# Controller_Nano_1_5.net
KiCad netlist of a schematic drawn in EAGLE
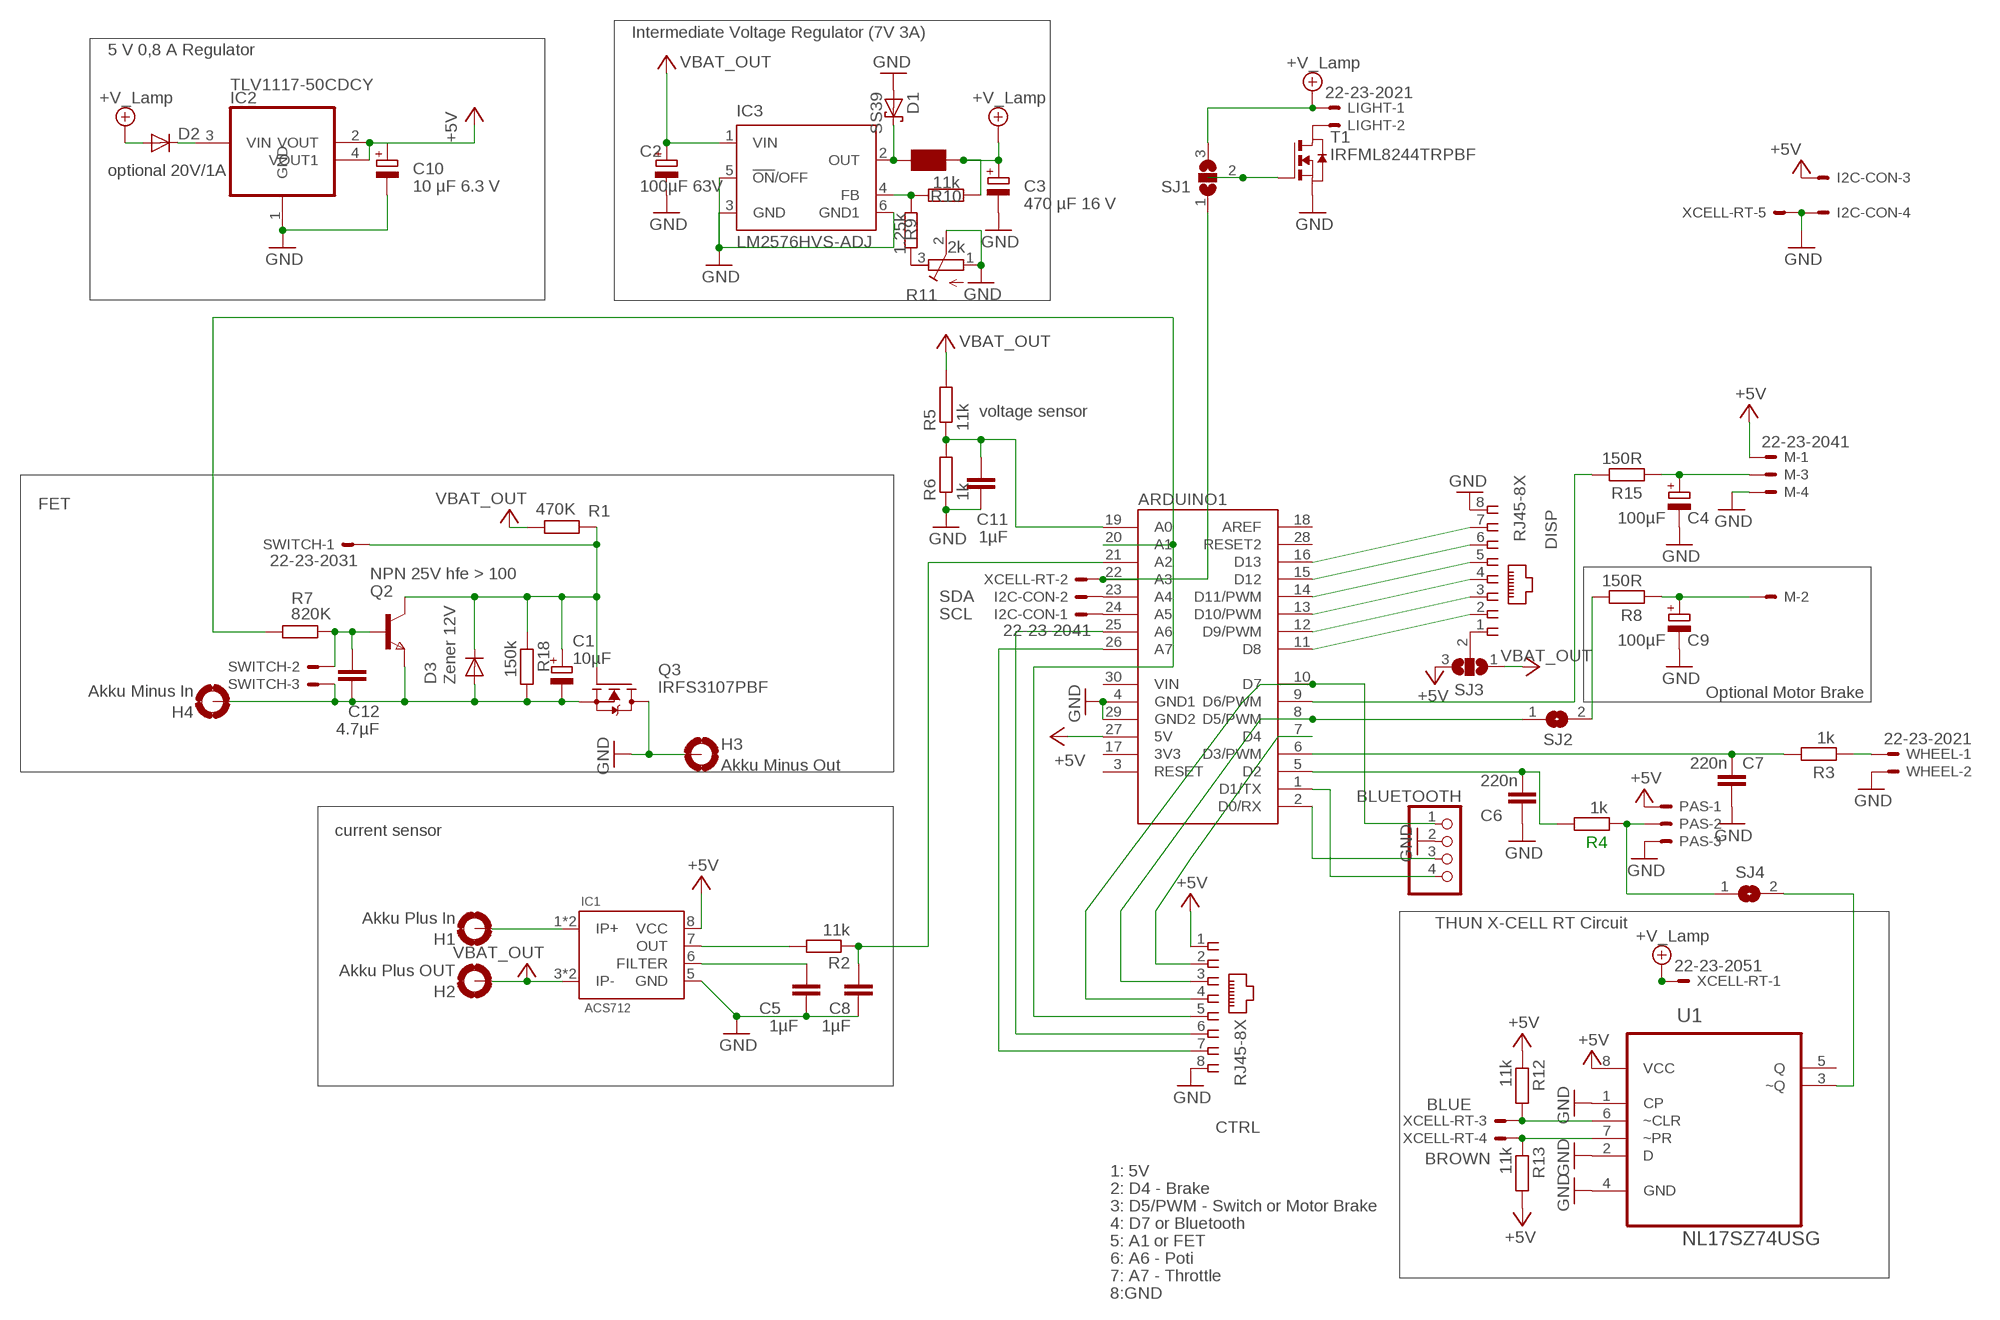
[diagram p0: schematic, sheet 1]

(export (version "E")
  (design (tool "Eeschema 10.0.6"))
  (components
    (comp (ref "ARDUINO1")
      (value "ARDUINO_NANO_CHECKED")
      (footprint "eagle-import:ARDUINO_NANO_CHECKED")
      (libsource (lib "eagle-import") (part "ARDUINO_NANO_CHECKED"))
    )
    (comp (ref "BLUETOOTH")
      (value "PINHD-1X4")
      (footprint "eagle-import:1X04")
      (libsource (lib "eagle-import") (part "PINHD-1X4"))
    )
    (comp (ref "C1")
      (value "10µF")
      (footprint "eagle-import:E2-5")
      (libsource (lib "eagle-import") (part "CPOL-EUE2-5"))
    )
    (comp (ref "C2")
      (value "100µF 63V")
      (footprint "eagle-import:E3,5-8")
      (libsource (lib "eagle-import") (part "CPOL-EUE3.5-8"))
    )
    (comp (ref "C3")
      (value "470 µF 16 V")
      (footprint "eagle-import:E3,5-8")
      (libsource (lib "eagle-import") (part "CPOL-EUE3.5-8"))
    )
    (comp (ref "C4")
      (value "100µF")
      (footprint "eagle-import:E2-5")
      (libsource (lib "eagle-import") (part "CPOL-EUE2-5"))
    )
    (comp (ref "C5")
      (value "1µF")
      (footprint "eagle-import:C0805")
      (libsource (lib "eagle-import") (part "C-EUC0805"))
    )
    (comp (ref "C6")
      (value "220n")
      (footprint "eagle-import:C0805")
      (libsource (lib "eagle-import") (part "C-EUC0805"))
    )
    (comp (ref "C7")
      (value "220n")
      (footprint "eagle-import:C0805")
      (libsource (lib "eagle-import") (part "C-EUC0805"))
    )
    (comp (ref "C8")
      (value "1µF")
      (footprint "eagle-import:C0805")
      (libsource (lib "eagle-import") (part "C-EUC0805"))
    )
    (comp (ref "C9")
      (value "100µF")
      (footprint "eagle-import:E2-5")
      (libsource (lib "eagle-import") (part "CPOL-EUE2-5"))
    )
    (comp (ref "C10")
      (value "10 µF 6.3 V")
      (footprint "eagle-import:E2-5")
      (libsource (lib "eagle-import") (part "CPOL-EUE2-5"))
    )
    (comp (ref "C11")
      (value "1µF")
      (footprint "eagle-import:C0805")
      (libsource (lib "eagle-import") (part "C-EUC0805"))
    )
    (comp (ref "C12")
      (value "4.7µF")
      (footprint "eagle-import:C0805")
      (libsource (lib "eagle-import") (part "C-EUC0805"))
    )
    (comp (ref "CTRL")
      (value "RJ45-8X")
      (footprint "eagle-import:RJ45-NO-SHIELD")
      (libsource (lib "eagle-import") (part "RJ45-8X"))
    )
    (comp (ref "D1")
      (value "SS39")
      (footprint "eagle-import:SMC")
      (libsource (lib "eagle-import") (part "SCHOTTKY-DIODESMC"))
    )
    (comp (ref "D2")
      (value "optional 20V/1A")
      (footprint "eagle-import:DO-214AC")
      (libsource (lib "eagle-import") (part "DIODE-DO-214AC"))
    )
    (comp (ref "D3")
      (value "Zener 12V")
      (footprint "eagle-import:SOD323-W")
      (libsource (lib "eagle-import") (part "DIODE-SOD323-W"))
    )
    (comp (ref "DISP")
      (value "RJ45-8X")
      (footprint "eagle-import:RJ45-NO-SHIELD")
      (libsource (lib "eagle-import") (part "RJ45-8X"))
    )
    (comp (ref "H1")
      (value "Akku Plus In")
      (footprint "eagle-import:2,8-PAD")
      (libsource (lib "eagle-import") (part "MOUNT-PAD-ROUND2.8"))
    )
    (comp (ref "H2")
      (value "Akku Plus OUT")
      (footprint "eagle-import:2,8-PAD")
      (libsource (lib "eagle-import") (part "MOUNT-PAD-ROUND2.8"))
    )
    (comp (ref "H3")
      (value "Akku Minus Out")
      (footprint "eagle-import:2,8-PAD")
      (libsource (lib "eagle-import") (part "MOUNT-PAD-ROUND2.8"))
    )
    (comp (ref "H4")
      (value "Akku Minus In")
      (footprint "eagle-import:2,8-PAD")
      (libsource (lib "eagle-import") (part "MOUNT-PAD-ROUND2.8"))
    )
    (comp (ref "I2C-CON")
      (value "22-23-2041")
      (footprint "eagle-import:22-23-2041")
      (fields (field (name "MF") "MOLEX"))
      (libsource (lib "eagle-import") (part "22-23-2041"))
    )
    (comp (ref "IC1")
      (value "ACS712")
      (footprint "eagle-import:MARTIN-SMD-IC_SO-8")
      (libsource (lib "eagle-import") (part "MARTIN-SMD-IC_ACS712"))
    )
    (comp (ref "IC2")
      (value "TLV1117-50CDCY")
      (footprint "eagle-import:SOT223")
      (fields (field (name "MPN") "REG1117"))
      (libsource (lib "eagle-import") (part "REG1117"))
    )
    (comp (ref "IC3")
      (value "LM2576HVS-ADJ")
      (footprint "eagle-import:TO263-5")
      (fields (field (name "MF") "NATIONAL SEMICONDUCTOR") (field (name "MPN") "LM2596S-ADJ/NOPB"))
      (libsource (lib "eagle-import") (part "LM2596S"))
    )
    (comp (ref "LIGHT")
      (value "22-23-2021")
      (footprint "eagle-import:22-23-2021")
      (fields
        (field (name "MF") "MOLEX")
        (field (name "MF_1") "MOLEX")
        (field (name "MPN") "22-23-2021")
        (field (name "OC_FARNELL") "1462926")
        (field (name "OC_NEWARK") "25C3832")
      )
      (libsource (lib "eagle-import") (part "22-23-2021"))
    )
    (comp (ref "M")
      (value "22-23-2041")
      (footprint "eagle-import:22-23-2041")
      (fields
        (field (name "MF") "MOLEX")
        (field (name "MPN") "22-23-2041")
        (field (name "OC_FARNELL") "1462920")
        (field (name "OC_NEWARK") "38C0355")
      )
      (libsource (lib "eagle-import") (part "22-23-2041"))
    )
    (comp (ref "PAS")
      (value "22-23-2031")
      (footprint "eagle-import:22-23-2031")
      (fields (field (name "MF") "MOLEX"))
      (libsource (lib "eagle-import") (part "22-23-2031"))
    )
    (comp (ref "Q2")
      (value "NPN 25V hfe > 100")
      (footprint "eagle-import:SOT-23")
      (fields (field (name "MPN") "DSS20201L-7"))
      (libsource (lib "eagle-import") (part "NPNSOT23"))
    )
    (comp (ref "Q3")
      (value "IRFS3107PBF")
      (footprint "eagle-import:TRANSISTOR-FET_TO263")
      (libsource (lib "eagle-import") (part "BUK663R7-75C"))
    )
    (comp (ref "R1")
      (value "470K")
      (footprint "eagle-import:R1206")
      (libsource (lib "eagle-import") (part "R-EU_R1206"))
    )
    (comp (ref "R2")
      (value "11k")
      (footprint "eagle-import:R1206")
      (libsource (lib "eagle-import") (part "R-EU_R1206"))
    )
    (comp (ref "R3")
      (value "1k")
      (footprint "eagle-import:R1206")
      (libsource (lib "eagle-import") (part "R-EU_R1206"))
    )
    (comp (ref "R4")
      (value "1k")
      (footprint "eagle-import:R1206")
      (libsource (lib "eagle-import") (part "R-EU_R1206"))
    )
    (comp (ref "R5")
      (value "11k")
      (footprint "eagle-import:R1206")
      (libsource (lib "eagle-import") (part "R-EU_R1206"))
    )
    (comp (ref "R6")
      (value "1k")
      (footprint "eagle-import:R1206")
      (libsource (lib "eagle-import") (part "R-EU_R1206"))
    )
    (comp (ref "R7")
      (value "820K")
      (footprint "eagle-import:R1206")
      (libsource (lib "eagle-import") (part "R-EU_R1206"))
    )
    (comp (ref "R8")
      (value "150R")
      (footprint "eagle-import:R1206")
      (libsource (lib "eagle-import") (part "R-EU_R1206"))
    )
    (comp (ref "R9")
      (value "1.25k")
      (footprint "eagle-import:R1206")
      (libsource (lib "eagle-import") (part "R-EU_R1206"))
    )
    (comp (ref "R10")
      (value "11k")
      (footprint "eagle-import:R1206")
      (libsource (lib "eagle-import") (part "R-EU_R1206"))
    )
    (comp (ref "R11")
      (value "2k")
      (footprint "eagle-import:RTRIM3103")
      (libsource (lib "eagle-import") (part "R-TRIMM3103"))
    )
    (comp (ref "R12")
      (value "11k")
      (footprint "eagle-import:R1206")
      (libsource (lib "eagle-import") (part "R-EU_R1206"))
    )
    (comp (ref "R13")
      (value "11k")
      (footprint "eagle-import:R1206")
      (libsource (lib "eagle-import") (part "R-EU_R1206"))
    )
    (comp (ref "R15")
      (value "150R")
      (footprint "eagle-import:R1206")
      (libsource (lib "eagle-import") (part "R-EU_R1206"))
    )
    (comp (ref "R18")
      (value "150k")
      (footprint "eagle-import:R1206")
      (libsource (lib "eagle-import") (part "R-EU_R1206"))
    )
    (comp (ref "SJ1")
      (value "SJ2WW")
      (footprint "eagle-import:SJ_2W")
      (libsource (lib "eagle-import") (part "SJ2WW"))
    )
    (comp (ref "SJ2") (value "SJ") (footprint "eagle-import:SJ") (libsource (lib "eagle-import") (part "SJ")))
    (comp (ref "SJ3")
      (value "SJ2WW")
      (footprint "eagle-import:SJ_2W")
      (libsource (lib "eagle-import") (part "SJ2WW"))
    )
    (comp (ref "SJ4") (value "SJ") (footprint "eagle-import:SJ") (libsource (lib "eagle-import") (part "SJ")))
    (comp (ref "SWITCH")
      (value "22-23-2031")
      (footprint "eagle-import:22-23-2031")
      (fields
        (field (name "MF") "MOLEX")
        (field (name "MPN") "22-23-2031")
        (field (name "OC_FARNELL") "1462950")
        (field (name "OC_NEWARK") "30C0862")
      )
      (libsource (lib "eagle-import") (part "22-23-2031"))
    )
    (comp (ref "T1")
      (value "IRFML8244TRPBF")
      (footprint "eagle-import:SOT-23")
      (libsource (lib "eagle-import") (part "NMOSSOT23"))
    )
    (comp (ref "U$1")
      (value "PIST-151")
      (footprint "eagle-import:PIST-151")
      (libsource (lib "eagle-import") (part "PIST-151"))
    )
    (comp (ref "U1")
      (value "NL17SZ74USG")
      (footprint "eagle-import:SOP50P310X90-8N")
      (libsource (lib "eagle-import") (part "NL17SZ74USG"))
    )
    (comp (ref "WHEEL")
      (value "22-23-2021")
      (footprint "eagle-import:22-23-2021")
      (fields (field (name "MF") "MOLEX"))
      (libsource (lib "eagle-import") (part "22-23-2021"))
    )
    (comp (ref "XCELL-RT")
      (value "22-23-2051")
      (footprint "eagle-import:22-23-2051")
      (fields (field (name "MF") "MOLEX"))
      (libsource (lib "eagle-import") (part "22-23-2051"))
    )
  )
  (nets
    (net (code "1") (name "+5V") (class "Default")
      (node (ref "ARDUINO1") (pin "27") (pinfunction "5V_27") (pintype "power_in"))
      (node (ref "C10") (pin "+") (pinfunction "+_+") (pintype "passive"))
      (node (ref "CTRL") (pin "1") (pinfunction "1_1") (pintype "passive"))
      (node (ref "I2C-CON") (pin "3") (pinfunction "S_3") (pintype "passive"))
      (node (ref "IC1") (pin "8") (pinfunction "VCC_8") (pintype "power_in"))
      (node (ref "IC2") (pin "2") (pinfunction "VOUT_2") (pintype "output"))
      (node (ref "IC2") (pin "4") (pinfunction "VOUT1_4") (pintype "output"))
      (node (ref "M") (pin "1") (pinfunction "S_1") (pintype "passive"))
      (node (ref "PAS") (pin "1") (pinfunction "S_1") (pintype "passive"))
      (node (ref "R12") (pin "1") (pinfunction "1_1") (pintype "passive"))
      (node (ref "R13") (pin "2") (pinfunction "2_2") (pintype "passive"))
      (node (ref "SJ3") (pin "3") (pinfunction "3_3") (pintype "passive"))
      (node (ref "U1") (pin "8") (pinfunction "VCC_8") (pintype "power_in"))
    )
    (net (code "2") (name "+V_Lamp") (class "Default")
      (node (ref "C3") (pin "+") (pinfunction "+_+") (pintype "passive"))
      (node (ref "D2") (pin "A") (pinfunction "A_A") (pintype "passive"))
      (node (ref "LIGHT") (pin "1") (pinfunction "S_1") (pintype "passive"))
      (node (ref "R10") (pin "1") (pinfunction "1_1") (pintype "passive"))
      (node (ref "SJ1") (pin "3") (pinfunction "3_3") (pintype "passive"))
      (node (ref "U$1") (pin "P$2") (pinfunction "P$2_P$2") (pintype "bidirectional"))
      (node (ref "XCELL-RT") (pin "1") (pinfunction "S_1") (pintype "passive"))
    )
    (net (code "3") (name "/3V3") (class "Default")
      (node (ref "ARDUINO1") (pin "17") (pinfunction "3V3_17") (pintype "power_in"))
    )
    (net (code "4") (name "GND") (class "Default")
      (node (ref "ARDUINO1") (pin "29") (pinfunction "GND2_29") (pintype "power_in"))
      (node (ref "ARDUINO1") (pin "4") (pinfunction "GND1_4") (pintype "power_in"))
      (node (ref "BLUETOOTH") (pin "2") (pinfunction "2_2") (pintype "passive"))
      (node (ref "C10") (pin "-") (pinfunction "-_-") (pintype "passive"))
      (node (ref "C11") (pin "2") (pinfunction "2_2") (pintype "passive"))
      (node (ref "C2") (pin "-") (pinfunction "-_-") (pintype "passive"))
      (node (ref "C3") (pin "-") (pinfunction "-_-") (pintype "passive"))
      (node (ref "C4") (pin "-") (pinfunction "-_-") (pintype "passive"))
      (node (ref "C5") (pin "2") (pinfunction "2_2") (pintype "passive"))
      (node (ref "C6") (pin "2") (pinfunction "2_2") (pintype "passive"))
      (node (ref "C7") (pin "2") (pinfunction "2_2") (pintype "passive"))
      (node (ref "C8") (pin "2") (pinfunction "2_2") (pintype "passive"))
      (node (ref "C9") (pin "-") (pinfunction "-_-") (pintype "passive"))
      (node (ref "CTRL") (pin "8") (pinfunction "8_8") (pintype "passive"))
      (node (ref "D1") (pin "A") (pinfunction "A_A") (pintype "passive"))
      (node (ref "DISP") (pin "8") (pinfunction "8_8") (pintype "passive"))
      (node (ref "H3") (pin "B2,8") (pinfunction "MOUNT_B2,8") (pintype "passive"))
      (node (ref "I2C-CON") (pin "4") (pinfunction "S_4") (pintype "passive"))
      (node (ref "IC1") (pin "5") (pinfunction "GND_5") (pintype "power_in"))
      (node (ref "IC2") (pin "1") (pinfunction "GND_1") (pintype "power_in"))
      (node (ref "IC3") (pin "3") (pinfunction "GND_3") (pintype "power_in"))
      (node (ref "IC3") (pin "5") (pinfunction "~{ON}/OFF_5") (pintype "input"))
      (node (ref "IC3") (pin "6") (pinfunction "GND1_6") (pintype "power_in"))
      (node (ref "M") (pin "4") (pinfunction "S_4") (pintype "passive"))
      (node (ref "PAS") (pin "3") (pinfunction "S_3") (pintype "passive"))
      (node (ref "Q3") (pin "2D") (pinfunction "D_2D") (pintype "passive"))
      (node (ref "R11") (pin "1") (pinfunction "E_1") (pintype "passive"))
      (node (ref "R11") (pin "2") (pinfunction "S_2") (pintype "passive"))
      (node (ref "R6") (pin "1") (pinfunction "1_1") (pintype "passive"))
      (node (ref "T1") (pin "2") (pinfunction "S_2") (pintype "passive"))
      (node (ref "U1") (pin "1") (pinfunction "CP_1") (pintype "input"))
      (node (ref "U1") (pin "2") (pinfunction "D_2") (pintype "input"))
      (node (ref "U1") (pin "4") (pinfunction "GND_4") (pintype "passive"))
      (node (ref "WHEEL") (pin "2") (pinfunction "S_2") (pintype "passive"))
      (node (ref "XCELL-RT") (pin "5") (pinfunction "S_5") (pintype "passive"))
    )
    (net (code "5") (name "Net-(ARDUINO1-A0)") (class "Default")
      (node (ref "ARDUINO1") (pin "19") (pinfunction "A0_19") (pintype "bidirectional"))
      (node (ref "C11") (pin "1") (pinfunction "1_1") (pintype "passive"))
      (node (ref "R5") (pin "1") (pinfunction "1_1") (pintype "passive"))
      (node (ref "R6") (pin "2") (pinfunction "2_2") (pintype "passive"))
    )
    (net (code "6") (name "Net-(ARDUINO1-A1)") (class "Default")
      (node (ref "ARDUINO1") (pin "20") (pinfunction "A1_20") (pintype "bidirectional"))
      (node (ref "CTRL") (pin "5") (pinfunction "5_5") (pintype "passive"))
      (node (ref "R7") (pin "2") (pinfunction "2_2") (pintype "passive"))
    )
    (net (code "7") (name "Net-(ARDUINO1-A2)") (class "Default")
      (node (ref "ARDUINO1") (pin "21") (pinfunction "A2_21") (pintype "bidirectional"))
      (node (ref "C8") (pin "1") (pinfunction "1_1") (pintype "passive"))
      (node (ref "R2") (pin "1") (pinfunction "1_1") (pintype "passive"))
    )
    (net (code "8") (name "Net-(ARDUINO1-A3)") (class "Default")
      (node (ref "ARDUINO1") (pin "22") (pinfunction "A3_22") (pintype "bidirectional"))
      (node (ref "SJ1") (pin "1") (pinfunction "1_1") (pintype "passive"))
      (node (ref "XCELL-RT") (pin "2") (pinfunction "S_2") (pintype "passive"))
    )
    (net (code "9") (name "Net-(ARDUINO1-A4)") (class "Default")
      (node (ref "ARDUINO1") (pin "23") (pinfunction "A4_23") (pintype "bidirectional"))
      (node (ref "I2C-CON") (pin "2") (pinfunction "S_2") (pintype "passive"))
    )
    (net (code "10") (name "Net-(ARDUINO1-A5)") (class "Default")
      (node (ref "ARDUINO1") (pin "24") (pinfunction "A5_24") (pintype "bidirectional"))
      (node (ref "I2C-CON") (pin "1") (pinfunction "S_1") (pintype "passive"))
    )
    (net (code "11") (name "Net-(ARDUINO1-A6)") (class "Default")
      (node (ref "ARDUINO1") (pin "25") (pinfunction "A6_25") (pintype "bidirectional"))
      (node (ref "CTRL") (pin "6") (pinfunction "6_6") (pintype "passive"))
    )
    (net (code "12") (name "Net-(ARDUINO1-A7)") (class "Default")
      (node (ref "ARDUINO1") (pin "26") (pinfunction "A7_26") (pintype "bidirectional"))
      (node (ref "CTRL") (pin "7") (pinfunction "7_7") (pintype "passive"))
    )
    (net (code "13") (name "Net-(ARDUINO1-D0{slash}RX)") (class "Default")
      (node (ref "ARDUINO1") (pin "2") (pinfunction "D0/RX_2") (pintype "bidirectional"))
      (node (ref "BLUETOOTH") (pin "3") (pinfunction "3_3") (pintype "passive"))
    )
    (net (code "14") (name "Net-(ARDUINO1-D1{slash}TX)") (class "Default")
      (node (ref "ARDUINO1") (pin "1") (pinfunction "D1/TX_1") (pintype "bidirectional"))
      (node (ref "BLUETOOTH") (pin "4") (pinfunction "4_4") (pintype "passive"))
    )
    (net (code "15") (name "Net-(ARDUINO1-D2)") (class "Default")
      (node (ref "ARDUINO1") (pin "5") (pinfunction "D2_5") (pintype "bidirectional"))
      (node (ref "C6") (pin "1") (pinfunction "1_1") (pintype "passive"))
      (node (ref "R4") (pin "2") (pinfunction "2_2") (pintype "passive"))
    )
    (net (code "16") (name "Net-(ARDUINO1-D3{slash}PWM)") (class "Default")
      (node (ref "ARDUINO1") (pin "6") (pinfunction "D3/PWM_6") (pintype "bidirectional"))
      (node (ref "C7") (pin "1") (pinfunction "1_1") (pintype "passive"))
      (node (ref "R3") (pin "2") (pinfunction "2_2") (pintype "passive"))
    )
    (net (code "17") (name "Net-(ARDUINO1-D4)") (class "Default")
      (node (ref "ARDUINO1") (pin "7") (pinfunction "D4_7") (pintype "bidirectional"))
      (node (ref "CTRL") (pin "2") (pinfunction "2_2") (pintype "passive"))
    )
    (net (code "18") (name "Net-(ARDUINO1-D5{slash}PWM)") (class "Default")
      (node (ref "ARDUINO1") (pin "8") (pinfunction "D5/PWM_8") (pintype "bidirectional"))
      (node (ref "CTRL") (pin "3") (pinfunction "3_3") (pintype "passive"))
      (node (ref "SJ2") (pin "1") (pinfunction "1_1") (pintype "passive"))
    )
    (net (code "19") (name "Net-(ARDUINO1-D6{slash}PWM)") (class "Default")
      (node (ref "ARDUINO1") (pin "9") (pinfunction "D6/PWM_9") (pintype "bidirectional"))
      (node (ref "R15") (pin "2") (pinfunction "2_2") (pintype "passive"))
    )
    (net (code "20") (name "Net-(ARDUINO1-D7)") (class "Default")
      (node (ref "ARDUINO1") (pin "10") (pinfunction "D7_10") (pintype "bidirectional"))
      (node (ref "BLUETOOTH") (pin "1") (pinfunction "1_1") (pintype "passive"))
      (node (ref "CTRL") (pin "4") (pinfunction "4_4") (pintype "passive"))
    )
    (net (code "21") (name "Net-(ARDUINO1-D8)") (class "Default")
      (node (ref "ARDUINO1") (pin "11") (pinfunction "D8_11") (pintype "bidirectional"))
      (node (ref "DISP") (pin "2") (pinfunction "2_2") (pintype "passive"))
    )
    (net (code "22") (name "Net-(ARDUINO1-D9{slash}PWM)") (class "Default")
      (node (ref "ARDUINO1") (pin "12") (pinfunction "D9/PWM_12") (pintype "bidirectional"))
      (node (ref "DISP") (pin "3") (pinfunction "3_3") (pintype "passive"))
    )
    (net (code "23") (name "Net-(ARDUINO1-D10{slash}PWM)") (class "Default")
      (node (ref "ARDUINO1") (pin "13") (pinfunction "D10/PWM_13") (pintype "bidirectional"))
      (node (ref "DISP") (pin "4") (pinfunction "4_4") (pintype "passive"))
    )
    (net (code "24") (name "Net-(ARDUINO1-D11{slash}PWM)") (class "Default")
      (node (ref "ARDUINO1") (pin "14") (pinfunction "D11/PWM_14") (pintype "bidirectional"))
      (node (ref "DISP") (pin "5") (pinfunction "5_5") (pintype "passive"))
    )
    (net (code "25") (name "Net-(ARDUINO1-D12)") (class "Default")
      (node (ref "ARDUINO1") (pin "15") (pinfunction "D12_15") (pintype "bidirectional"))
      (node (ref "DISP") (pin "6") (pinfunction "6_6") (pintype "passive"))
    )
    (net (code "26") (name "Net-(ARDUINO1-D13)") (class "Default")
      (node (ref "ARDUINO1") (pin "16") (pinfunction "D13_16") (pintype "bidirectional"))
      (node (ref "DISP") (pin "7") (pinfunction "7_7") (pintype "passive"))
    )
    (net (code "27") (name "Net-(DISP-Pad1)") (class "Default")
      (node (ref "DISP") (pin "1") (pinfunction "1_1") (pintype "passive"))
      (node (ref "SJ3") (pin "2") (pinfunction "2_2") (pintype "passive"))
    )
    (net (code "28") (name "Net-(H1-MOUNT)") (class "Default")
      (node (ref "H1") (pin "B2,8") (pinfunction "MOUNT_B2,8") (pintype "passive"))
      (node (ref "IC1") (pin "1") (pinfunction "IP+_1") (pintype "bidirectional"))
      (node (ref "IC1") (pin "2") (pinfunction "IP+_2") (pintype "bidirectional"))
    )
    (net (code "29") (name "Net-(H4-MOUNT)") (class "Default")
      (node (ref "C1") (pin "-") (pinfunction "-_-") (pintype "passive"))
      (node (ref "C12") (pin "2") (pinfunction "2_2") (pintype "passive"))
      (node (ref "D3") (pin "A") (pinfunction "A_A") (pintype "passive"))
      (node (ref "H4") (pin "B2,8") (pinfunction "MOUNT_B2,8") (pintype "passive"))
      (node (ref "Q2") (pin "2") (pinfunction "E_2") (pintype "passive"))
      (node (ref "Q3") (pin "3S") (pinfunction "S_3S") (pintype "passive"))
      (node (ref "R18") (pin "2") (pinfunction "2_2") (pintype "passive"))
      (node (ref "SWITCH") (pin "3") (pinfunction "S_3") (pintype "passive"))
    )
    (net (code "30") (name "Net-(IC1-FILTER)") (class "Default")
      (node (ref "C5") (pin "1") (pinfunction "1_1") (pintype "passive"))
      (node (ref "IC1") (pin "6") (pinfunction "FILTER_6") (pintype "bidirectional"))
    )
    (net (code "31") (name "Net-(IC1-OUT)") (class "Default")
      (node (ref "IC1") (pin "7") (pinfunction "OUT_7") (pintype "output"))
      (node (ref "R2") (pin "2") (pinfunction "2_2") (pintype "passive"))
    )
    (net (code "32") (name "Net-(IC2-VIN)") (class "Default")
      (node (ref "D2") (pin "C") (pinfunction "C_C") (pintype "passive"))
      (node (ref "IC2") (pin "3") (pinfunction "VIN_3") (pintype "input"))
    )
    (net (code "33") (name "Net-(IC3-FB)") (class "Default")
      (node (ref "IC3") (pin "4") (pinfunction "FB_4") (pintype "input"))
      (node (ref "R10") (pin "2") (pinfunction "2_2") (pintype "passive"))
      (node (ref "R9") (pin "2") (pinfunction "2_2") (pintype "passive"))
    )
    (net (code "34") (name "Net-(IC3-OUT)") (class "Default")
      (node (ref "D1") (pin "C") (pinfunction "C_C") (pintype "passive"))
      (node (ref "IC3") (pin "2") (pinfunction "OUT_2") (pintype "output"))
      (node (ref "U$1") (pin "P$1") (pinfunction "P$1_P$1") (pintype "bidirectional"))
    )
    (net (code "35") (name "Net-(LIGHTB-S)") (class "Default")
      (node (ref "LIGHT") (pin "2") (pinfunction "S_2") (pintype "passive"))
      (node (ref "T1") (pin "1") (pinfunction "D_1") (pintype "passive"))
    )
    (net (code "36") (name "Net-(MB-S)") (class "Default")
      (node (ref "C9") (pin "+") (pinfunction "+_+") (pintype "passive"))
      (node (ref "M") (pin "2") (pinfunction "S_2") (pintype "passive"))
      (node (ref "R8") (pin "1") (pinfunction "1_1") (pintype "passive"))
    )
    (net (code "37") (name "Net-(MC-S)") (class "Default")
      (node (ref "C4") (pin "+") (pinfunction "+_+") (pintype "passive"))
      (node (ref "M") (pin "3") (pinfunction "S_3") (pintype "passive"))
      (node (ref "R15") (pin "1") (pinfunction "1_1") (pintype "passive"))
    )
    (net (code "38") (name "Net-(PASB-S)") (class "Default")
      (node (ref "PAS") (pin "2") (pinfunction "S_2") (pintype "passive"))
      (node (ref "R4") (pin "1") (pinfunction "1_1") (pintype "passive"))
      (node (ref "SJ4") (pin "1") (pinfunction "1_1") (pintype "passive"))
    )
    (net (code "39") (name "Net-(Q2-B)") (class "Default")
      (node (ref "C12") (pin "1") (pinfunction "1_1") (pintype "passive"))
      (node (ref "Q2") (pin "3") (pinfunction "B_3") (pintype "passive"))
      (node (ref "R7") (pin "1") (pinfunction "1_1") (pintype "passive"))
      (node (ref "SWITCH") (pin "2") (pinfunction "S_2") (pintype "passive"))
    )
    (net (code "40") (name "Net-(Q2-C)") (class "Default")
      (node (ref "C1") (pin "+") (pinfunction "+_+") (pintype "passive"))
      (node (ref "D3") (pin "C") (pinfunction "C_C") (pintype "passive"))
      (node (ref "Q2") (pin "1") (pinfunction "C_1") (pintype "passive"))
      (node (ref "Q3") (pin "1G") (pinfunction "G_1G") (pintype "passive"))
      (node (ref "R1") (pin "2") (pinfunction "2_2") (pintype "passive"))
      (node (ref "R18") (pin "1") (pinfunction "1_1") (pintype "passive"))
      (node (ref "SWITCH") (pin "1") (pinfunction "S_1") (pintype "passive"))
    )
    (net (code "41") (name "Net-(R8-Pad2)") (class "Default")
      (node (ref "R8") (pin "2") (pinfunction "2_2") (pintype "passive"))
      (node (ref "SJ2") (pin "2") (pinfunction "2_2") (pintype "passive"))
    )
    (net (code "42") (name "Net-(R11-A)") (class "Default")
      (node (ref "R11") (pin "3") (pinfunction "A_3") (pintype "passive"))
      (node (ref "R9") (pin "1") (pinfunction "1_1") (pintype "passive"))
    )
    (net (code "43") (name "Net-(T1-G)") (class "Default")
      (node (ref "SJ1") (pin "2") (pinfunction "2_2") (pintype "passive"))
      (node (ref "T1") (pin "3") (pinfunction "G_3") (pintype "passive"))
    )
    (net (code "44") (name "Net-(U1-~{CLR})") (class "Default")
      (node (ref "R12") (pin "2") (pinfunction "2_2") (pintype "passive"))
      (node (ref "U1") (pin "6") (pinfunction "~{CLR}_6") (pintype "input"))
      (node (ref "XCELL-RT") (pin "3") (pinfunction "S_3") (pintype "passive"))
    )
    (net (code "45") (name "Net-(U1-~{PR})") (class "Default")
      (node (ref "R13") (pin "1") (pinfunction "1_1") (pintype "passive"))
      (node (ref "U1") (pin "7") (pinfunction "~{PR}_7") (pintype "input"))
      (node (ref "XCELL-RT") (pin "4") (pinfunction "S_4") (pintype "passive"))
    )
    (net (code "46") (name "Net-(U1-~{Q})") (class "Default")
      (node (ref "SJ4") (pin "2") (pinfunction "2_2") (pintype "passive"))
      (node (ref "U1") (pin "3") (pinfunction "~{Q}_3") (pintype "output"))
    )
    (net (code "47") (name "Net-(WHEELA-S)") (class "Default")
      (node (ref "R3") (pin "1") (pinfunction "1_1") (pintype "passive"))
      (node (ref "WHEEL") (pin "1") (pinfunction "S_1") (pintype "passive"))
    )
    (net (code "48") (name "VBAT_OUT") (class "Default")
      (node (ref "C2") (pin "+") (pinfunction "+_+") (pintype "passive"))
      (node (ref "H2") (pin "B2,8") (pinfunction "MOUNT_B2,8") (pintype "passive"))
      (node (ref "IC1") (pin "3") (pinfunction "IP-_3") (pintype "bidirectional"))
      (node (ref "IC1") (pin "4") (pinfunction "IP-_4") (pintype "bidirectional"))
      (node (ref "IC3") (pin "1") (pinfunction "VIN_1") (pintype "input"))
      (node (ref "R1") (pin "1") (pinfunction "1_1") (pintype "passive"))
      (node (ref "R5") (pin "2") (pinfunction "2_2") (pintype "passive"))
      (node (ref "SJ3") (pin "1") (pinfunction "1_1") (pintype "passive"))
    )
    (net (code "49") (name "unconnected-(ARDUINO1-AREF-Pad18)") (class "Default")
      (node (ref "ARDUINO1") (pin "18") (pinfunction "AREF_18") (pintype "bidirectional"))
    )
    (net (code "50") (name "unconnected-(ARDUINO1-RESET-Pad3)") (class "Default")
      (node (ref "ARDUINO1") (pin "3") (pinfunction "RESET_3") (pintype "bidirectional"))
    )
    (net (code "51") (name "unconnected-(ARDUINO1-RESET2-Pad28)") (class "Default")
      (node (ref "ARDUINO1") (pin "28") (pinfunction "RESET2_28") (pintype "bidirectional"))
    )
    (net (code "52") (name "unconnected-(ARDUINO1-VIN-Pad30)") (class "Default")
      (node (ref "ARDUINO1") (pin "30") (pinfunction "VIN_30") (pintype "bidirectional"))
    )
    (net (code "53") (name "unconnected-(U1-Q-Pad5)") (class "Default")
      (node (ref "U1") (pin "5") (pinfunction "Q_5") (pintype "output"))
    )
  )
)
